# REV_1.net
KiCad netlist of a schematic drawn in EAGLE
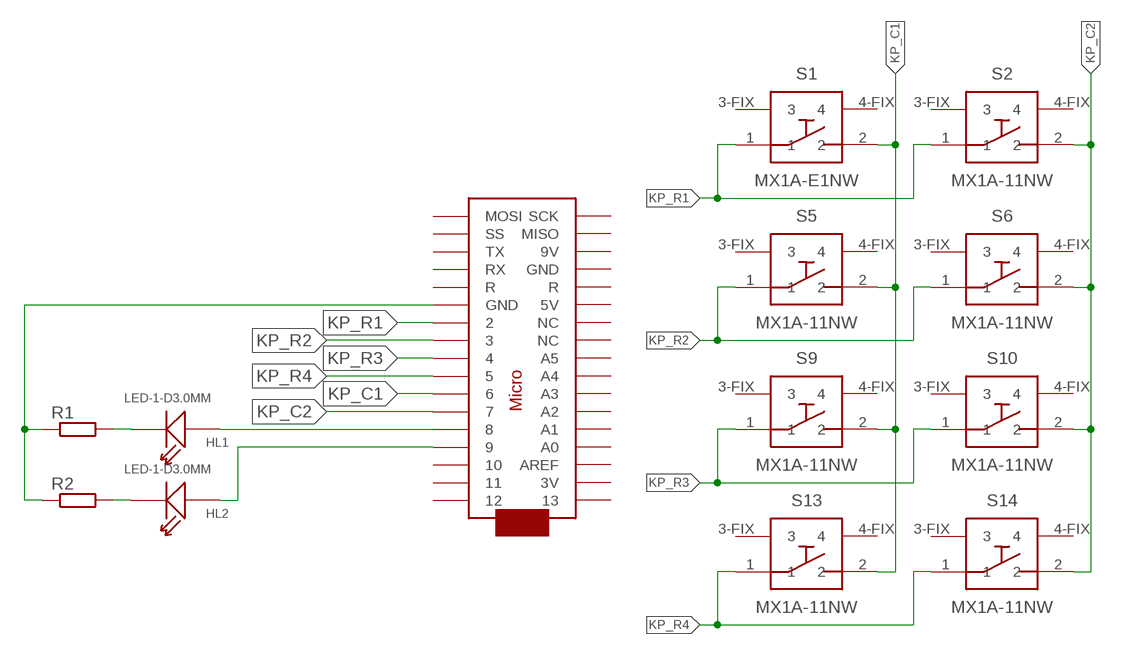
[diagram p0: schematic, sheet 1]

(export (version "E")
  (design (tool "Eeschema 10.0.6"))
  (components
    (comp (ref "HL1")
      (value "LED-1-D3.0MM")
      (footprint "eagle-import:LED2-2.54-D3.0MM")
      (libsource (lib "eagle-import") (part "LED-1-D3.0MM"))
    )
    (comp (ref "HL2")
      (value "LED-1-D3.0MM")
      (footprint "eagle-import:LED2-2.54-D3.0MM")
      (libsource (lib "eagle-import") (part "LED-1-D3.0MM"))
    )
    (comp (ref "R1")
      (value "R-EU_VTA52")
      (footprint "eagle-import:VTA52")
      (libsource (lib "eagle-import") (part "R-EU_VTA52"))
    )
    (comp (ref "R2")
      (value "R-EU_VTA52")
      (footprint "eagle-import:VTA52")
      (libsource (lib "eagle-import") (part "R-EU_VTA52"))
    )
    (comp (ref "S1")
      (value "MX1A-E1NW")
      (footprint "eagle-import:MX1A-11NW_1")
      (fields (field (name "MANUFACTURER_PART_NUMBER") "MX1A-11NW"))
      (libsource (lib "eagle-import") (part "MX1A-11NW"))
    )
    (comp (ref "S2")
      (value "MX1A-11NW")
      (footprint "eagle-import:MX1A-11NW_1")
      (libsource (lib "eagle-import") (part "MX1A-11NW"))
    )
    (comp (ref "S5")
      (value "MX1A-11NW")
      (footprint "eagle-import:MX1A-11NW_1")
      (libsource (lib "eagle-import") (part "MX1A-11NW"))
    )
    (comp (ref "S6")
      (value "MX1A-11NW")
      (footprint "eagle-import:MX1A-11NW_1")
      (libsource (lib "eagle-import") (part "MX1A-11NW"))
    )
    (comp (ref "S9")
      (value "MX1A-11NW")
      (footprint "eagle-import:MX1A-11NW_1")
      (libsource (lib "eagle-import") (part "MX1A-11NW"))
    )
    (comp (ref "S10")
      (value "MX1A-11NW")
      (footprint "eagle-import:MX1A-11NW_1")
      (libsource (lib "eagle-import") (part "MX1A-11NW"))
    )
    (comp (ref "S13")
      (value "MX1A-11NW")
      (footprint "eagle-import:MX1A-11NW_1")
      (libsource (lib "eagle-import") (part "MX1A-11NW"))
    )
    (comp (ref "S14")
      (value "MX1A-11NW")
      (footprint "eagle-import:MX1A-11NW_1")
      (libsource (lib "eagle-import") (part "MX1A-11NW"))
    )
    (comp (ref "U$2")
      (value "ARDUINOMICRO")
      (footprint "eagle-import:ARDUINOMICRO")
      (libsource (lib "eagle-import") (part "ARDUINOMICRO"))
    )
  )
  (nets
    (net (code "1") (name "KP_C1") (class "Default")
      (node (ref "S1") (pin "2") (pinfunction "2_2") (pintype "input"))
      (node (ref "S13") (pin "2") (pinfunction "2_2") (pintype "input"))
      (node (ref "S5") (pin "2") (pinfunction "2_2") (pintype "input"))
      (node (ref "S9") (pin "2") (pinfunction "2_2") (pintype "input"))
      (node (ref "U$2") (pin "P$7") (pinfunction "6_P$7") (pintype "bidirectional"))
    )
    (net (code "2") (name "KP_C2") (class "Default")
      (node (ref "S10") (pin "2") (pinfunction "2_2") (pintype "input"))
      (node (ref "S14") (pin "2") (pinfunction "2_2") (pintype "input"))
      (node (ref "S2") (pin "2") (pinfunction "2_2") (pintype "input"))
      (node (ref "S6") (pin "2") (pinfunction "2_2") (pintype "input"))
      (node (ref "U$2") (pin "P$6") (pinfunction "7_P$6") (pintype "bidirectional"))
    )
    (net (code "3") (name "KP_R1") (class "Default")
      (node (ref "S1") (pin "1") (pinfunction "1_1") (pintype "input"))
      (node (ref "S2") (pin "1") (pinfunction "1_1") (pintype "input"))
      (node (ref "U$2") (pin "P$11") (pinfunction "2_P$11") (pintype "bidirectional"))
    )
    (net (code "4") (name "KP_R2") (class "Default")
      (node (ref "S5") (pin "1") (pinfunction "1_1") (pintype "input"))
      (node (ref "S6") (pin "1") (pinfunction "1_1") (pintype "input"))
      (node (ref "U$2") (pin "P$10") (pinfunction "3_P$10") (pintype "bidirectional"))
    )
    (net (code "5") (name "KP_R3") (class "Default")
      (node (ref "S10") (pin "1") (pinfunction "1_1") (pintype "input"))
      (node (ref "S9") (pin "1") (pinfunction "1_1") (pintype "input"))
      (node (ref "U$2") (pin "P$9") (pinfunction "4_P$9") (pintype "bidirectional"))
    )
    (net (code "6") (name "KP_R4") (class "Default")
      (node (ref "S13") (pin "1") (pinfunction "1_1") (pintype "input"))
      (node (ref "S14") (pin "1") (pinfunction "1_1") (pintype "input"))
      (node (ref "U$2") (pin "P$8") (pinfunction "5_P$8") (pintype "bidirectional"))
    )
    (net (code "7") (name "Net-(HL1-Pad-)") (class "Default")
      (node (ref "HL1") (pin "-") (pinfunction "-_-") (pintype "passive"))
      (node (ref "R1") (pin "2") (pinfunction "2_2") (pintype "passive"))
    )
    (net (code "8") (name "Net-(HL2-Pad-)") (class "Default")
      (node (ref "HL2") (pin "-") (pinfunction "-_-") (pintype "passive"))
      (node (ref "R2") (pin "2") (pinfunction "2_2") (pintype "passive"))
    )
    (net (code "9") (name "Net-(R1-Pad1)") (class "Default")
      (node (ref "R1") (pin "1") (pinfunction "1_1") (pintype "passive"))
      (node (ref "R2") (pin "1") (pinfunction "1_1") (pintype "passive"))
      (node (ref "U$2") (pin "P$21") (pinfunction "GND_P$21") (pintype "bidirectional"))
    )
    (net (code "10") (name "Net-(U$2-8)") (class "Default")
      (node (ref "HL1") (pin "+") (pinfunction "+_+") (pintype "passive"))
      (node (ref "U$2") (pin "P$5") (pinfunction "8_P$5") (pintype "bidirectional"))
    )
    (net (code "11") (name "Net-(U$2-9)") (class "Default")
      (node (ref "HL2") (pin "+") (pinfunction "+_+") (pintype "passive"))
      (node (ref "U$2") (pin "P$4") (pinfunction "9_P$4") (pintype "bidirectional"))
    )
    (net (code "12") (name "unconnected-(S1-3-Pad3-FIX)") (class "Default")
      (node (ref "S1") (pin "3-FIX") (pinfunction "3_3-FIX") (pintype "input"))
    )
    (net (code "13") (name "unconnected-(S1-4-Pad4-FIX)") (class "Default")
      (node (ref "S1") (pin "4-FIX") (pinfunction "4_4-FIX") (pintype "input"))
    )
    (net (code "14") (name "unconnected-(S2-3-Pad3-FIX)") (class "Default")
      (node (ref "S2") (pin "3-FIX") (pinfunction "3_3-FIX") (pintype "input"))
    )
    (net (code "15") (name "unconnected-(S2-4-Pad4-FIX)") (class "Default")
      (node (ref "S2") (pin "4-FIX") (pinfunction "4_4-FIX") (pintype "input"))
    )
    (net (code "16") (name "unconnected-(S5-3-Pad3-FIX)") (class "Default")
      (node (ref "S5") (pin "3-FIX") (pinfunction "3_3-FIX") (pintype "input"))
    )
    (net (code "17") (name "unconnected-(S5-4-Pad4-FIX)") (class "Default")
      (node (ref "S5") (pin "4-FIX") (pinfunction "4_4-FIX") (pintype "input"))
    )
    (net (code "18") (name "unconnected-(S6-3-Pad3-FIX)") (class "Default")
      (node (ref "S6") (pin "3-FIX") (pinfunction "3_3-FIX") (pintype "input"))
    )
    (net (code "19") (name "unconnected-(S6-4-Pad4-FIX)") (class "Default")
      (node (ref "S6") (pin "4-FIX") (pinfunction "4_4-FIX") (pintype "input"))
    )
    (net (code "20") (name "unconnected-(S9-3-Pad3-FIX)") (class "Default")
      (node (ref "S9") (pin "3-FIX") (pinfunction "3_3-FIX") (pintype "input"))
    )
    (net (code "21") (name "unconnected-(S9-4-Pad4-FIX)") (class "Default")
      (node (ref "S9") (pin "4-FIX") (pinfunction "4_4-FIX") (pintype "input"))
    )
    (net (code "22") (name "unconnected-(S10-3-Pad3-FIX)") (class "Default")
      (node (ref "S10") (pin "3-FIX") (pinfunction "3_3-FIX") (pintype "input"))
    )
    (net (code "23") (name "unconnected-(S10-4-Pad4-FIX)") (class "Default")
      (node (ref "S10") (pin "4-FIX") (pinfunction "4_4-FIX") (pintype "input"))
    )
    (net (code "24") (name "unconnected-(S13-3-Pad3-FIX)") (class "Default")
      (node (ref "S13") (pin "3-FIX") (pinfunction "3_3-FIX") (pintype "input"))
    )
    (net (code "25") (name "unconnected-(S13-4-Pad4-FIX)") (class "Default")
      (node (ref "S13") (pin "4-FIX") (pinfunction "4_4-FIX") (pintype "input"))
    )
    (net (code "26") (name "unconnected-(S14-3-Pad3-FIX)") (class "Default")
      (node (ref "S14") (pin "3-FIX") (pinfunction "3_3-FIX") (pintype "input"))
    )
    (net (code "27") (name "unconnected-(S14-4-Pad4-FIX)") (class "Default")
      (node (ref "S14") (pin "4-FIX") (pinfunction "4_4-FIX") (pintype "input"))
    )
    (net (code "28") (name "unconnected-(U$2-3V-PadP$33)") (class "Default")
      (node (ref "U$2") (pin "P$33") (pinfunction "3V_P$33") (pintype "bidirectional"))
    )
    (net (code "29") (name "unconnected-(U$2-5V-PadP$23)") (class "Default")
      (node (ref "U$2") (pin "P$23") (pinfunction "5V_P$23") (pintype "bidirectional"))
    )
    (net (code "30") (name "unconnected-(U$2-9V-PadP$20)") (class "Default")
      (node (ref "U$2") (pin "P$20") (pinfunction "9V_P$20") (pintype "bidirectional"))
    )
    (net (code "31") (name "unconnected-(U$2-10-PadP$3)") (class "Default")
      (node (ref "U$2") (pin "P$3") (pinfunction "10_P$3") (pintype "bidirectional"))
    )
    (net (code "32") (name "unconnected-(U$2-11-PadP$2)") (class "Default")
      (node (ref "U$2") (pin "P$2") (pinfunction "11_P$2") (pintype "bidirectional"))
    )
    (net (code "33") (name "unconnected-(U$2-12-PadP$1)") (class "Default")
      (node (ref "U$2") (pin "P$1") (pinfunction "12_P$1") (pintype "bidirectional"))
    )
    (net (code "34") (name "unconnected-(U$2-13-PadP$34)") (class "Default")
      (node (ref "U$2") (pin "P$34") (pinfunction "13_P$34") (pintype "bidirectional"))
    )
    (net (code "35") (name "unconnected-(U$2-A0-PadP$31)") (class "Default")
      (node (ref "U$2") (pin "P$31") (pinfunction "A0_P$31") (pintype "bidirectional"))
    )
    (net (code "36") (name "unconnected-(U$2-A1-PadP$30)") (class "Default")
      (node (ref "U$2") (pin "P$30") (pinfunction "A1_P$30") (pintype "bidirectional"))
    )
    (net (code "37") (name "unconnected-(U$2-A2-PadP$29)") (class "Default")
      (node (ref "U$2") (pin "P$29") (pinfunction "A2_P$29") (pintype "bidirectional"))
    )
    (net (code "38") (name "unconnected-(U$2-A3-PadP$28)") (class "Default")
      (node (ref "U$2") (pin "P$28") (pinfunction "A3_P$28") (pintype "bidirectional"))
    )
    (net (code "39") (name "unconnected-(U$2-A4-PadP$27)") (class "Default")
      (node (ref "U$2") (pin "P$27") (pinfunction "A4_P$27") (pintype "bidirectional"))
    )
    (net (code "40") (name "unconnected-(U$2-A5-PadP$26)") (class "Default")
      (node (ref "U$2") (pin "P$26") (pinfunction "A5_P$26") (pintype "bidirectional"))
    )
    (net (code "41") (name "unconnected-(U$2-AREF-PadP$32)") (class "Default")
      (node (ref "U$2") (pin "P$32") (pinfunction "AREF_P$32") (pintype "bidirectional"))
    )
    (net (code "42") (name "unconnected-(U$2-GND-PadP$12)") (class "Default")
      (node (ref "U$2") (pin "P$12") (pinfunction "GND_P$12") (pintype "bidirectional"))
    )
    (net (code "43") (name "unconnected-(U$2-MISO-PadP$19)") (class "Default")
      (node (ref "U$2") (pin "P$19") (pinfunction "MISO_P$19") (pintype "bidirectional"))
    )
    (net (code "44") (name "unconnected-(U$2-MOSI-PadP$17)") (class "Default")
      (node (ref "U$2") (pin "P$17") (pinfunction "MOSI_P$17") (pintype "bidirectional"))
    )
    (net (code "45") (name "unconnected-(U$2-NC-PadP$24)") (class "Default")
      (node (ref "U$2") (pin "P$24") (pinfunction "NC_P$24") (pintype "bidirectional"))
    )
    (net (code "46") (name "unconnected-(U$2-NC-PadP$25)") (class "Default")
      (node (ref "U$2") (pin "P$25") (pinfunction "NC_P$25") (pintype "bidirectional"))
    )
    (net (code "47") (name "unconnected-(U$2-R-PadP$13)") (class "Default")
      (node (ref "U$2") (pin "P$13") (pinfunction "R_P$13") (pintype "bidirectional"))
    )
    (net (code "48") (name "unconnected-(U$2-R-PadP$22)") (class "Default")
      (node (ref "U$2") (pin "P$22") (pinfunction "R_P$22") (pintype "bidirectional"))
    )
    (net (code "49") (name "unconnected-(U$2-RX-PadP$14)") (class "Default")
      (node (ref "U$2") (pin "P$14") (pinfunction "RX_P$14") (pintype "bidirectional"))
    )
    (net (code "50") (name "unconnected-(U$2-SCK-PadP$18)") (class "Default")
      (node (ref "U$2") (pin "P$18") (pinfunction "SCK_P$18") (pintype "bidirectional"))
    )
    (net (code "51") (name "unconnected-(U$2-SS-PadP$16)") (class "Default")
      (node (ref "U$2") (pin "P$16") (pinfunction "SS_P$16") (pintype "bidirectional"))
    )
    (net (code "52") (name "unconnected-(U$2-TX-PadP$15)") (class "Default")
      (node (ref "U$2") (pin "P$15") (pinfunction "TX_P$15") (pintype "bidirectional"))
    )
  )
)
